# SK-Connector.net
KiCad netlist of a schematic drawn in Altium Designer
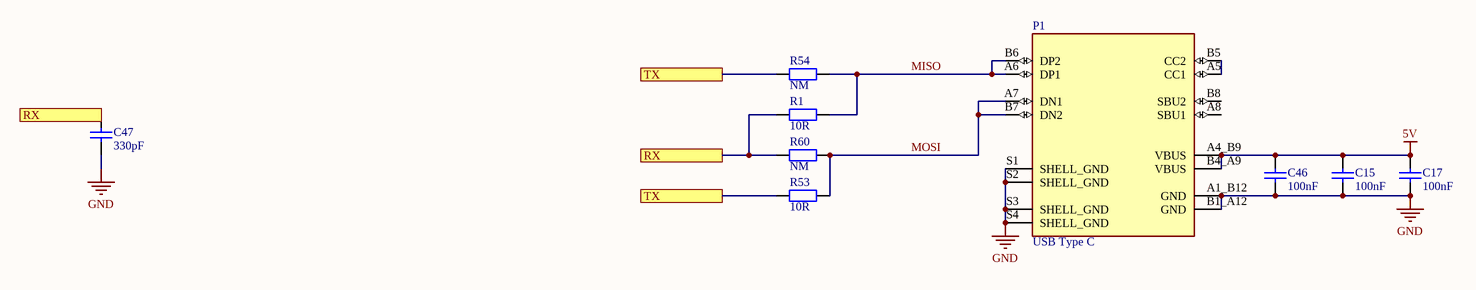
[diagram p0: SK-Connector.SchDoc]

(export (version "E")
  (design (tool "Eeschema 10.0.6"))
  (components
    (comp (ref "C15")
      (value "100nF")
      (footprint "SMH_RES0805-STD")
      (description "Capacitor")
      (fields (field (name "PUBLISHER") "Altium Limited"))
      (libsource (lib "Miscellaneous Devices") (part "Cap"))
    )
    (comp (ref "C17")
      (value "100nF")
      (footprint "SMH_RES0805-STD")
      (description "Capacitor")
      (fields (field (name "PUBLISHER") "Altium Limited"))
      (libsource (lib "Miscellaneous Devices") (part "Cap"))
    )
    (comp (ref "C46")
      (value "100nF")
      (footprint "SMH_RES0805-STD")
      (description "Capacitor")
      (fields (field (name "PUBLISHER") "Altium Limited"))
      (libsource (lib "Miscellaneous Devices") (part "Cap"))
    )
    (comp (ref "C47")
      (value "330pF")
      (footprint "SMH_RES0805-STD")
      (description "Capacitor")
      (fields (field (name "PUBLISHER") "Altium Limited"))
      (libsource (lib "Miscellaneous Devices") (part "Cap"))
    )
    (comp (ref "P1")
      (value "USB Type C")
      (footprint "SMH_USB_C")
      (libsource (lib "Mlib") (part "USB Type C"))
    )
    (comp (ref "R1")
      (value "10R")
      (footprint "SMH_RES0805-STD")
      (description "Resistor")
      (fields (field (name "PUBLISHER") "Altium Limited"))
      (libsource (lib "") (part "Res2_1"))
    )
    (comp (ref "R53")
      (value "10R")
      (footprint "SMH_RES0805-STD")
      (description "Resistor")
      (fields (field (name "PUBLISHER") "Altium Limited"))
      (libsource (lib "Miscellaneous Devices") (part "Res2"))
    )
    (comp (ref "R54")
      (value "NM")
      (footprint "SMH_RES0805-STD")
      (description "Resistor")
      (fields (field (name "PUBLISHER") "Altium Limited"))
      (libsource (lib "Miscellaneous Devices") (part "Res2"))
    )
    (comp (ref "R60")
      (value "NM")
      (footprint "SMH_RES0805-STD")
      (description "Resistor")
      (fields (field (name "PUBLISHER") "Altium Limited"))
      (libsource (lib "") (part "Res2_1"))
    )
  )
  (nets
    (net (code "1") (name "/MISO") (class "Default")
      (node (ref "P1") (pin "A6") (pinfunction "DP1_A6") (pintype "bidirectional"))
      (node (ref "P1") (pin "B6") (pinfunction "DP2_B6") (pintype "bidirectional"))
      (node (ref "R1") (pin "1") (pinfunction "1_1") (pintype "passive"))
      (node (ref "R54") (pin "2") (pinfunction "2_2") (pintype "passive"))
    )
    (net (code "2") (name "/MOSI") (class "Default")
      (node (ref "P1") (pin "A7") (pinfunction "DN1_A7") (pintype "bidirectional"))
      (node (ref "P1") (pin "B7") (pinfunction "DN2_B7") (pintype "bidirectional"))
      (node (ref "R53") (pin "2") (pinfunction "2_2") (pintype "passive"))
      (node (ref "R60") (pin "1") (pinfunction "1_1") (pintype "passive"))
    )
    (net (code "3") (name "/RX") (class "Default")
      (node (ref "C47") (pin "1") (pinfunction "1_1") (pintype "passive"))
      (node (ref "R1") (pin "2") (pinfunction "2_2") (pintype "passive"))
      (node (ref "R60") (pin "2") (pinfunction "2_2") (pintype "passive"))
    )
    (net (code "4") (name "/TX") (class "Default")
      (node (ref "R53") (pin "1") (pinfunction "1_1") (pintype "passive"))
      (node (ref "R54") (pin "1") (pinfunction "1_1") (pintype "passive"))
    )
    (net (code "5") (name "5V") (class "Default")
      (node (ref "C15") (pin "1") (pinfunction "1_1") (pintype "passive"))
      (node (ref "C17") (pin "1") (pinfunction "1_1") (pintype "passive"))
      (node (ref "C46") (pin "1") (pinfunction "1_1") (pintype "passive"))
      (node (ref "P1") (pin "A4_B9") (pinfunction "VBUS_A4_B9") (pintype "power_in"))
      (node (ref "P1") (pin "B4_A9") (pinfunction "VBUS_B4_A9") (pintype "power_in"))
    )
    (net (code "6") (name "GND") (class "Default")
      (node (ref "C15") (pin "2") (pinfunction "2_2") (pintype "passive"))
      (node (ref "C17") (pin "2") (pinfunction "2_2") (pintype "passive"))
      (node (ref "C46") (pin "2") (pinfunction "2_2") (pintype "passive"))
      (node (ref "C47") (pin "2") (pinfunction "2_2") (pintype "passive"))
      (node (ref "P1") (pin "A1_B12") (pinfunction "GND_A1_B12") (pintype "power_in"))
      (node (ref "P1") (pin "B1_A12") (pinfunction "GND_B1_A12") (pintype "power_in"))
      (node (ref "P1") (pin "S1") (pinfunction "SHELL_GND_S1") (pintype "power_in"))
      (node (ref "P1") (pin "S2") (pinfunction "SHELL_GND_S2") (pintype "power_in"))
      (node (ref "P1") (pin "S3") (pinfunction "SHELL_GND_S3") (pintype "power_in"))
      (node (ref "P1") (pin "S4") (pinfunction "SHELL_GND_S4") (pintype "power_in"))
    )
    (net (code "7") (name "Net-(P1-CC1)") (class "Default")
      (node (ref "P1") (pin "A5") (pinfunction "CC1_A5") (pintype "bidirectional"))
      (node (ref "P1") (pin "B5") (pinfunction "CC2_B5") (pintype "bidirectional"))
    )
    (net (code "8") (name "unconnected-(P1-SBU1-PadA8)") (class "Default")
      (node (ref "P1") (pin "A8") (pinfunction "SBU1_A8") (pintype "bidirectional"))
    )
    (net (code "9") (name "unconnected-(P1-SBU2-PadB8)") (class "Default")
      (node (ref "P1") (pin "B8") (pinfunction "SBU2_B8") (pintype "bidirectional"))
    )
  )
)
